# spi_current_sensor.net
KiCad netlist of a schematic drawn in EAGLE
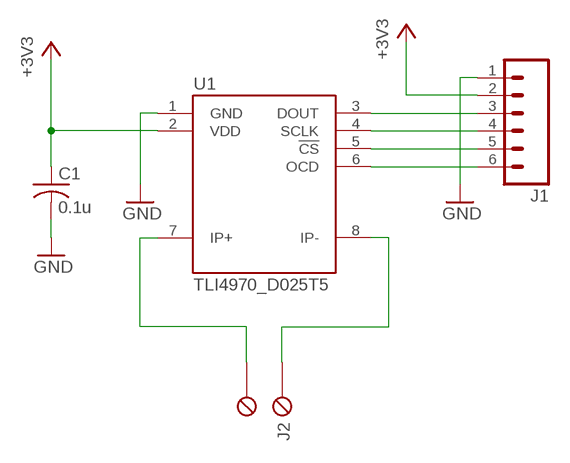
[diagram p0: schematic, sheet 1]

(export (version "E")
  (design (tool "Eeschema 10.0.6"))
  (components
    (comp (ref "C1")
      (value "0.1u")
      (footprint "eagle-import:C025-025X050")
      (libsource (lib "eagle-import") (part "C-US025-025X050"))
    )
    (comp (ref "J1")
      (value "M06LONGPADS")
      (footprint "eagle-import:1X06_LONGPADS")
      (libsource (lib "eagle-import") (part "M06LONGPADS"))
    )
    (comp (ref "J2")
      (value "METALTEX-2")
      (footprint "eagle-import:METALTEX-2")
      (libsource (lib "eagle-import") (part "METALTEX-2"))
    )
    (comp (ref "U1")
      (value "TLI4970_D025T5")
      (footprint "eagle-import:TLI4970_D025T5")
      (libsource (lib "eagle-import") (part "TLI4970_D025T5"))
    )
  )
  (nets
    (net (code "1") (name "+3V3") (class "Default")
      (node (ref "C1") (pin "1") (pinfunction "1_1") (pintype "passive"))
      (node (ref "J1") (pin "2") (pinfunction "2_2") (pintype "passive"))
      (node (ref "U1") (pin "2") (pinfunction "VDD_2") (pintype "power_in"))
    )
    (net (code "2") (name "GND") (class "Default")
      (node (ref "C1") (pin "2") (pinfunction "2_2") (pintype "passive"))
      (node (ref "J1") (pin "1") (pinfunction "1_1") (pintype "passive"))
      (node (ref "U1") (pin "1") (pinfunction "GND_1") (pintype "power_in"))
    )
    (net (code "3") (name "Net-(U1-DOUT)") (class "Default")
      (node (ref "J1") (pin "3") (pinfunction "3_3") (pintype "passive"))
      (node (ref "U1") (pin "3") (pinfunction "DOUT_3") (pintype "output"))
    )
    (net (code "4") (name "Net-(U1-IP+)") (class "Default")
      (node (ref "J2") (pin "P2") (pinfunction "P2_P2") (pintype "bidirectional"))
      (node (ref "U1") (pin "7") (pinfunction "IP+_7") (pintype "input"))
    )
    (net (code "5") (name "Net-(U1-IP-)") (class "Default")
      (node (ref "J2") (pin "P1") (pinfunction "P1_P1") (pintype "bidirectional"))
      (node (ref "U1") (pin "8") (pinfunction "IP-_8") (pintype "output"))
    )
    (net (code "6") (name "Net-(U1-OCD)") (class "Default")
      (node (ref "J1") (pin "6") (pinfunction "6_6") (pintype "passive"))
      (node (ref "U1") (pin "6") (pinfunction "OCD_6") (pintype "output"))
    )
    (net (code "7") (name "Net-(U1-SCLK)") (class "Default")
      (node (ref "J1") (pin "4") (pinfunction "4_4") (pintype "passive"))
      (node (ref "U1") (pin "4") (pinfunction "SCLK_4") (pintype "input"))
    )
    (net (code "8") (name "Net-(U1-~{CS})") (class "Default")
      (node (ref "J1") (pin "5") (pinfunction "5_5") (pintype "passive"))
      (node (ref "U1") (pin "5") (pinfunction "~{CS}_5") (pintype "input"))
    )
  )
)
